# Power_supply.net
KiCad netlist of a schematic drawn in Altium Designer
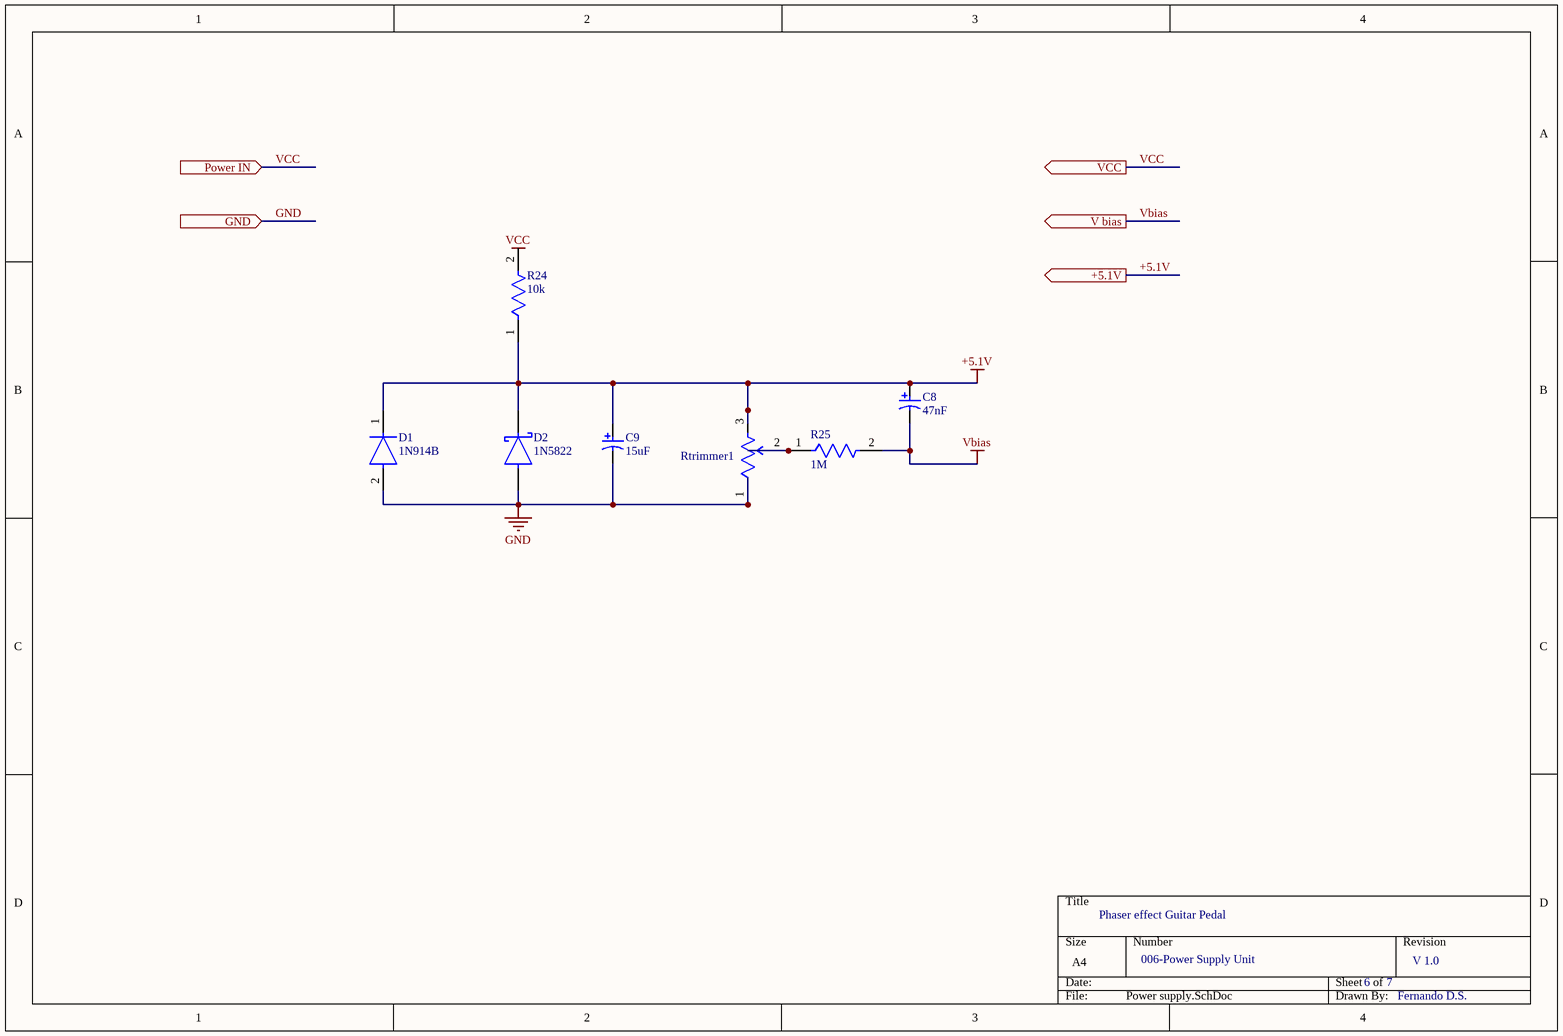
[diagram p0: Power supply.SchDoc]

(export (version "E")
  (design (tool "Eeschema 10.0.6"))
  (components
    (comp (ref "C8")
      (value "47nF")
      (footprint "NIC-PLF-10x13-2_V")
      (description "Aluminum Electrolytic Capacitor, 470 uF +/-20%, 10 V, -55 to 105 degC, 2-Pin THD, RoHS")
      (fields (field (name "MANUFACTURER") "Nichicon") (field (name "PARTNUMBER") "PLF1A471MDO1"))
      (libsource (lib "Altium Content Vault") (part "NIC-CAP-P-2"))
    )
    (comp (ref "C9")
      (value "15uF")
      (footprint "NIC-PLF-10x13-2_V")
      (description "Aluminum Electrolytic Capacitor, 470 uF +/-20%, 10 V, -55 to 105 degC, 2-Pin THD, RoHS")
      (fields (field (name "MANUFACTURER") "Nichicon") (field (name "PARTNUMBER") "PLF1A471MDO1"))
      (libsource (lib "Altium Content Vault") (part "NIC-CAP-P-2"))
    )
    (comp (ref "D1")
      (value "1N914B")
      (footprint "FP-017AG-MFG")
      (description "DIODE GEN PURP 100V 200MA DO35")
      (fields
        (field (name "OCTOPART") "https://octopart.com/1n914b-on+semiconductor-84323163")
        (field (name "MANUFACTURER") "ON Semiconductor")
      )
      (libsource (lib "Altium Content Vault") (part "d7152d700b627762746794eb795d46e"))
    )
    (comp (ref "D2")
      (value "1N5822")
      (footprint "FP-DO-201AD-MFG")
      (description "DIODE SCHOTTKY 40V 3A DO201AD")
      (fields
        (field (name "OCTOPART") "https://octopart.com/1n5822-stmicroelectronics-323225")
        (field (name "MANUFACTURER") "STMicroelectronics")
      )
      (libsource (lib "Altium Content Vault") (part "1d6ec82d83fb6aee721767c19dac4b9"))
    )
    (comp (ref "R24")
      (value "10k")
      (footprint "FP-MRS25-MFG")
      (fields (field (name "TOLERANCE") "1%"))
      (libsource (lib "Altium Content Vault") (part "1029c3af85768c4190bb7ad29bc67b5"))
    )
    (comp (ref "R25")
      (value "1M")
      (footprint "FP-MRS25-MFG")
      (fields (field (name "TOLERANCE") "1%"))
      (libsource (lib "Altium Content Vault") (part "1029c3af85768c4190bb7ad29bc67b5"))
    )
    (comp (ref "Rtrimmer1")
      (value "3362P-1-252LF")
      (footprint "FP-3362P-MFG")
      (description "3362P-1-252LF 1/4\" Sq, Thru-Hole, TRIMMER, 2.5 Kilohms, Cermet, Single Turn")
      (fields (field (name "TOLERANCE") "10%"))
      (libsource (lib "Altium Content Vault") (part "2dcfd2547301a7d3209a5e99acfd772"))
    )
  )
  (nets
    (net (code "1") (name "+5.1V") (class "Default")
      (node (ref "C8") (pin "1") (pinfunction "1_1") (pintype "passive"))
      (node (ref "C9") (pin "1") (pinfunction "1_1") (pintype "passive"))
      (node (ref "D1") (pin "1") (pinfunction "C_1") (pintype "passive"))
      (node (ref "D2") (pin "1") (pinfunction "C_1") (pintype "passive"))
      (node (ref "R24") (pin "1") (pinfunction "1_1") (pintype "passive"))
      (node (ref "Rtrimmer1") (pin "3") (pinfunction "CW_3") (pintype "passive"))
    )
    (net (code "2") (name "GND") (class "Default")
      (node (ref "C9") (pin "2") (pinfunction "2_2") (pintype "passive"))
      (node (ref "D1") (pin "2") (pinfunction "A_2") (pintype "passive"))
      (node (ref "D2") (pin "2") (pinfunction "A_2") (pintype "passive"))
      (node (ref "Rtrimmer1") (pin "1") (pinfunction "CCW_1") (pintype "passive"))
    )
    (net (code "3") (name "Net-(Rtrimmer1-WIPER)") (class "Default")
      (node (ref "R25") (pin "1") (pinfunction "1_1") (pintype "passive"))
      (node (ref "Rtrimmer1") (pin "2") (pinfunction "WIPER_2") (pintype "passive"))
    )
    (net (code "5") (name "Vbias") (class "Default")
      (node (ref "C8") (pin "2") (pinfunction "2_2") (pintype "passive"))
      (node (ref "R25") (pin "2") (pinfunction "2_2") (pintype "passive"))
    )
    (net (code "6") (name "unconnected-(R24-Pad2)") (class "Default")
      (node (ref "R24") (pin "2") (pinfunction "2_2") (pintype "passive"))
    )
  )
)
